# Servo.net
KiCad netlist of a schematic drawn in EAGLE
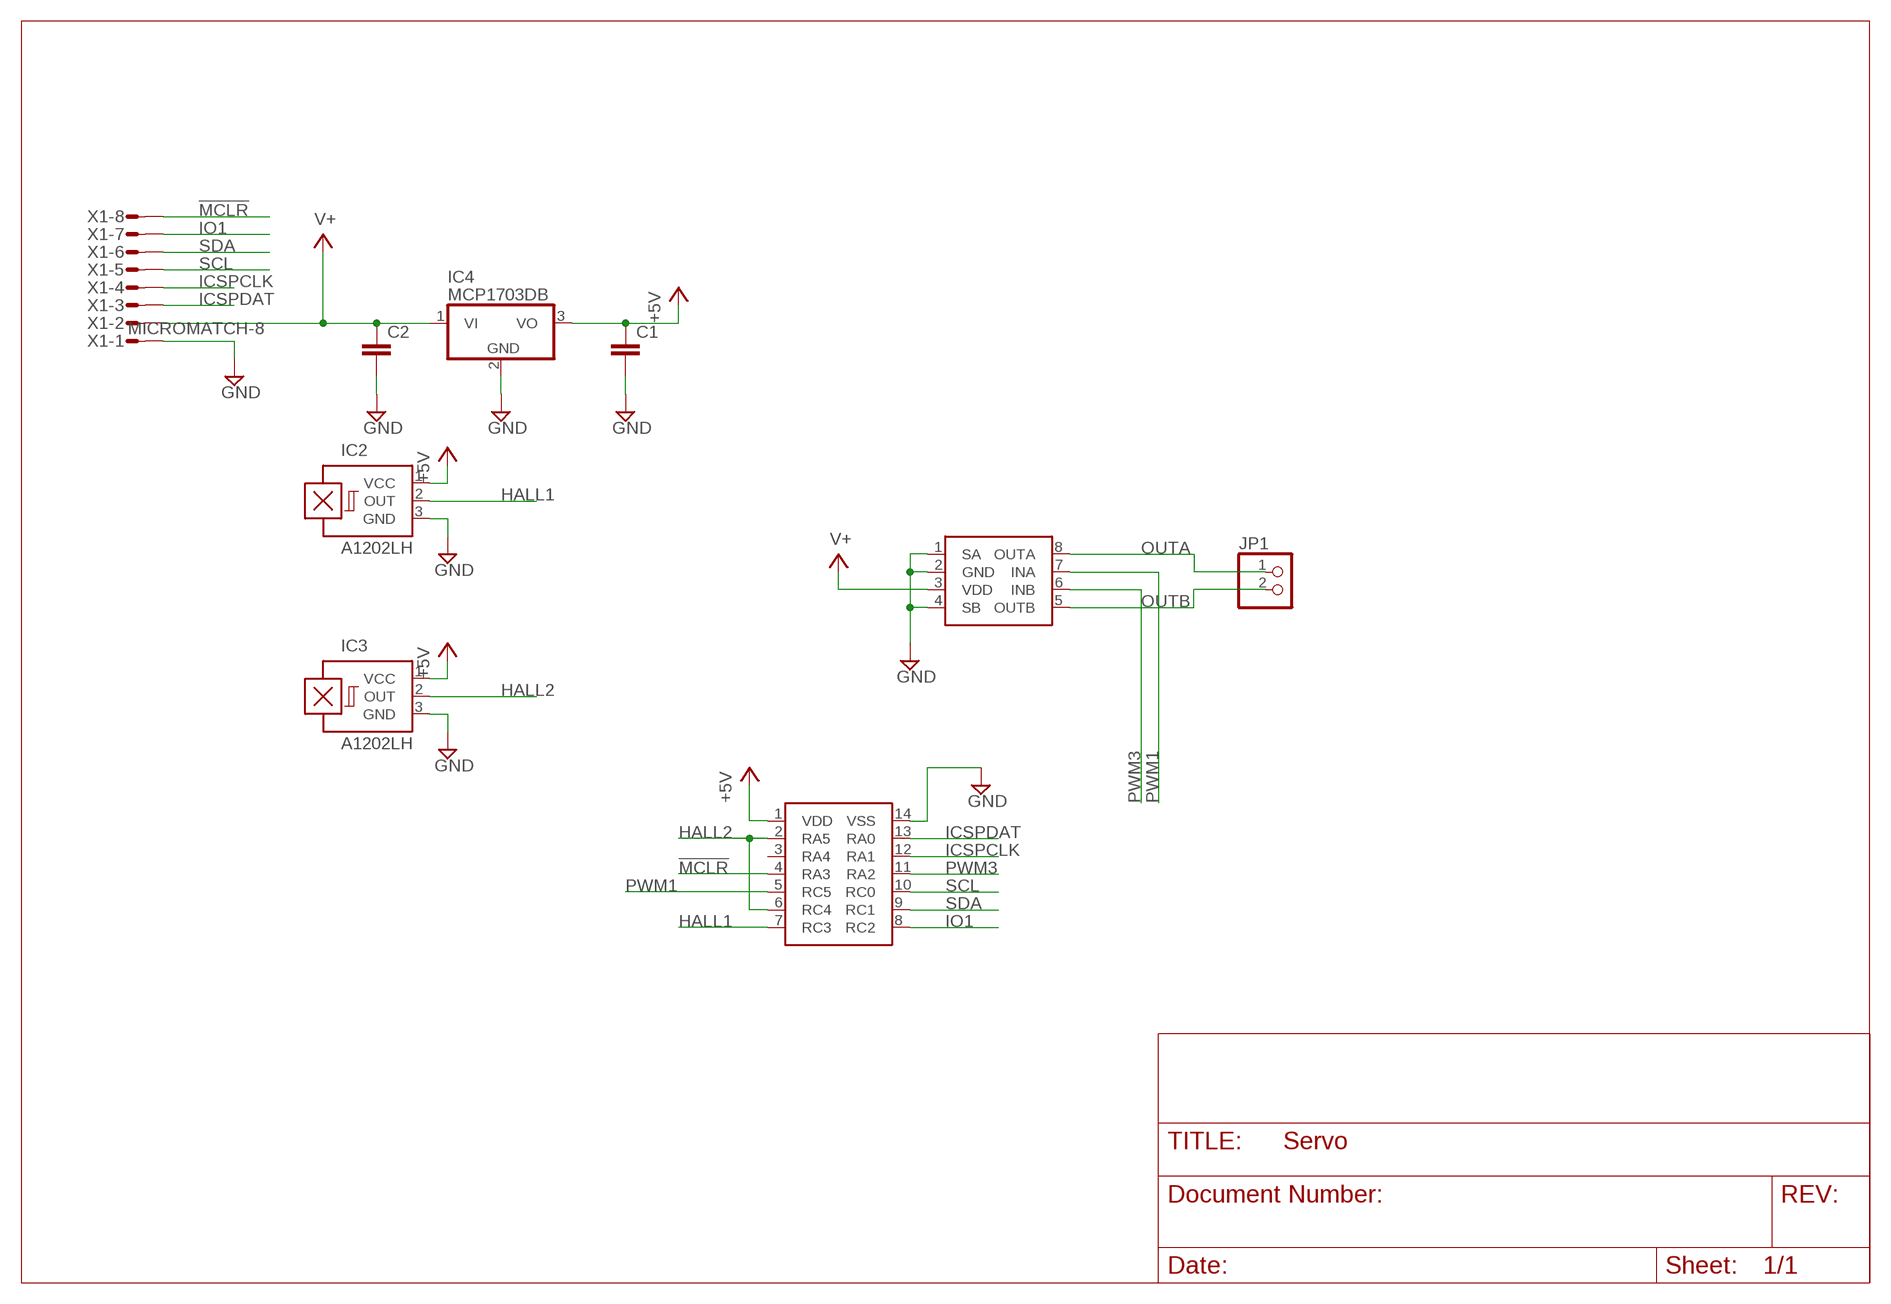
[diagram p0: schematic, sheet 1]

(export (version "E")
  (design (tool "Eeschema 10.0.6"))
  (components
    (comp (ref "C1")
      (value "C-EUC1206")
      (footprint "eagle-import:C1206")
      (libsource (lib "eagle-import") (part "C-EUC1206"))
    )
    (comp (ref "C2")
      (value "C-EUC1206")
      (footprint "eagle-import:C1206")
      (libsource (lib "eagle-import") (part "C-EUC1206"))
    )
    (comp (ref "IC2")
      (value "A1202LH")
      (footprint "eagle-import:SOT23-W")
      (libsource (lib "eagle-import") (part "A12?LH02"))
    )
    (comp (ref "IC3")
      (value "A1202LH")
      (footprint "eagle-import:SOT23-W")
      (libsource (lib "eagle-import") (part "A12?LH02"))
    )
    (comp (ref "IC4")
      (value "MCP1703DB")
      (footprint "eagle-import:SOT223")
      (libsource (lib "eagle-import") (part "MCP1703DB"))
    )
    (comp (ref "JP1")
      (value "PINHD-1X2")
      (footprint "eagle-import:1X02")
      (libsource (lib "eagle-import") (part "PINHD-1X2"))
    )
    (comp (ref "U$1")
      (value "PIC16F1503SOIC")
      (footprint "eagle-import:SO-14")
      (libsource (lib "eagle-import") (part "PIC16F1503SOIC"))
    )
    (comp (ref "U$2")
      (value "SI9986SO8")
      (footprint "eagle-import:SO-08")
      (libsource (lib "eagle-import") (part "SI9986SO8"))
    )
    (comp (ref "X1")
      (value "MICROMATCH-8")
      (footprint "eagle-import:MICROMATCH-8")
      (fields (field (name "MF") "FARNELL") (field (name "MPN") "7-215464-8"))
      (libsource (lib "eagle-import") (part "MICROMATCH-8"))
    )
  )
  (nets
    (net (code "1") (name "+5V") (class "Default")
      (node (ref "C1") (pin "1") (pinfunction "1_1") (pintype "passive"))
      (node (ref "IC2") (pin "1") (pinfunction "VCC_1") (pintype "power_in"))
      (node (ref "IC3") (pin "1") (pinfunction "VCC_1") (pintype "power_in"))
      (node (ref "IC4") (pin "3") (pinfunction "VO_3") (pintype "passive"))
      (node (ref "U$1") (pin "1") (pinfunction "VDD_1") (pintype "power_in"))
    )
    (net (code "2") (name "/HALL1") (class "Default")
      (node (ref "IC2") (pin "2") (pinfunction "OUT_2") (pintype "output"))
      (node (ref "U$1") (pin "7") (pinfunction "RC3_7") (pintype "bidirectional"))
    )
    (net (code "3") (name "/HALL2") (class "Default")
      (node (ref "IC3") (pin "2") (pinfunction "OUT_2") (pintype "output"))
      (node (ref "U$1") (pin "2") (pinfunction "RA5_2") (pintype "bidirectional"))
      (node (ref "U$1") (pin "6") (pinfunction "RC4_6") (pintype "bidirectional"))
    )
    (net (code "4") (name "/ICSPCLK") (class "Default")
      (node (ref "U$1") (pin "12") (pinfunction "RA1_12") (pintype "bidirectional"))
      (node (ref "X1") (pin "4") (pinfunction "S_4") (pintype "passive"))
    )
    (net (code "5") (name "/ICSPDAT") (class "Default")
      (node (ref "U$1") (pin "13") (pinfunction "RA0_13") (pintype "bidirectional"))
      (node (ref "X1") (pin "3") (pinfunction "S_3") (pintype "passive"))
    )
    (net (code "6") (name "/IO1") (class "Default")
      (node (ref "U$1") (pin "8") (pinfunction "RC2_8") (pintype "bidirectional"))
      (node (ref "X1") (pin "7") (pinfunction "S_7") (pintype "passive"))
    )
    (net (code "7") (name "/OUTA") (class "Default")
      (node (ref "JP1") (pin "1") (pinfunction "1_1") (pintype "passive"))
      (node (ref "U$2") (pin "8") (pinfunction "OUTA_8") (pintype "output"))
    )
    (net (code "8") (name "/OUTB") (class "Default")
      (node (ref "JP1") (pin "2") (pinfunction "2_2") (pintype "passive"))
      (node (ref "U$2") (pin "5") (pinfunction "OUTB_5") (pintype "output"))
    )
    (net (code "9") (name "/PWM1") (class "Default")
      (node (ref "U$1") (pin "5") (pinfunction "RC5_5") (pintype "bidirectional"))
      (node (ref "U$2") (pin "7") (pinfunction "INA_7") (pintype "input"))
    )
    (net (code "10") (name "/PWM3") (class "Default")
      (node (ref "U$1") (pin "11") (pinfunction "RA2_11") (pintype "bidirectional"))
      (node (ref "U$2") (pin "6") (pinfunction "INB_6") (pintype "input"))
    )
    (net (code "11") (name "/SCL") (class "Default")
      (node (ref "U$1") (pin "10") (pinfunction "RC0_10") (pintype "bidirectional"))
      (node (ref "X1") (pin "5") (pinfunction "S_5") (pintype "passive"))
    )
    (net (code "12") (name "/SDA") (class "Default")
      (node (ref "U$1") (pin "9") (pinfunction "RC1_9") (pintype "bidirectional"))
      (node (ref "X1") (pin "6") (pinfunction "S_6") (pintype "passive"))
    )
    (net (code "13") (name "/~{MCLR}") (class "Default")
      (node (ref "U$1") (pin "4") (pinfunction "RA3_4") (pintype "input"))
      (node (ref "X1") (pin "8") (pinfunction "S_8") (pintype "passive"))
    )
    (net (code "14") (name "GND") (class "Default")
      (node (ref "C1") (pin "2") (pinfunction "2_2") (pintype "passive"))
      (node (ref "C2") (pin "2") (pinfunction "2_2") (pintype "passive"))
      (node (ref "IC2") (pin "3") (pinfunction "GND_3") (pintype "power_in"))
      (node (ref "IC3") (pin "3") (pinfunction "GND_3") (pintype "power_in"))
      (node (ref "IC4") (pin "2") (pinfunction "GND_2") (pintype "passive"))
      (node (ref "U$1") (pin "14") (pinfunction "VSS_14") (pintype "power_in"))
      (node (ref "U$2") (pin "1") (pinfunction "SA_1") (pintype "power_in"))
      (node (ref "U$2") (pin "2") (pinfunction "GND_2") (pintype "power_in"))
      (node (ref "U$2") (pin "4") (pinfunction "SB_4") (pintype "power_in"))
      (node (ref "X1") (pin "1") (pinfunction "S_1") (pintype "passive"))
    )
    (net (code "15") (name "V+") (class "Default")
      (node (ref "C2") (pin "1") (pinfunction "1_1") (pintype "passive"))
      (node (ref "IC4") (pin "1") (pinfunction "VI_1") (pintype "input"))
      (node (ref "U$2") (pin "3") (pinfunction "VDD_3") (pintype "power_in"))
      (node (ref "X1") (pin "2") (pinfunction "S_2") (pintype "passive"))
    )
    (net (code "16") (name "unconnected-(U$1-RA4-Pad3)") (class "Default")
      (node (ref "U$1") (pin "3") (pinfunction "RA4_3") (pintype "bidirectional"))
    )
  )
)
